# Triggerboard.net
KiCad netlist of a schematic drawn in EAGLE
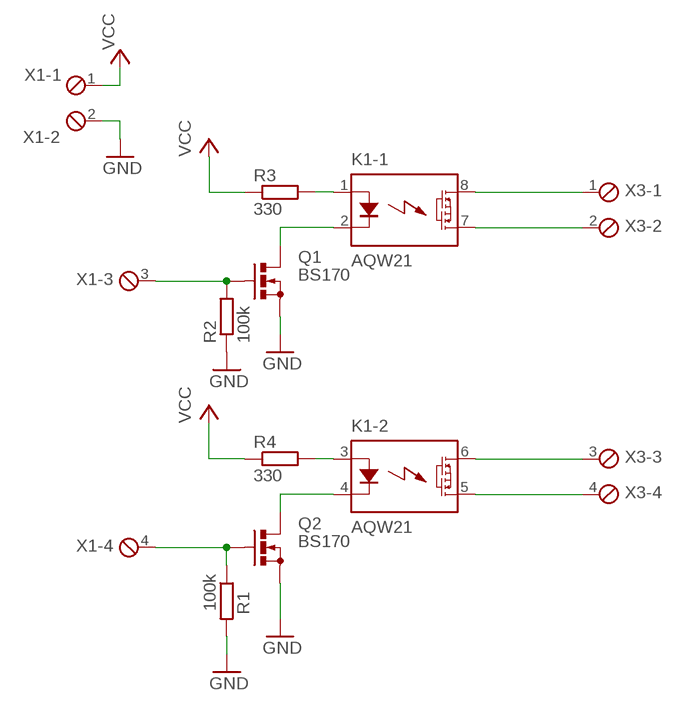
[diagram p0: schematic, sheet 1]

(export (version "E")
  (design (tool "Eeschema 10.0.6"))
  (components
    (comp (ref "K1")
      (value "AQW21")
      (footprint "eagle-import:DIL08")
      (fields
        (field (name "MF") "PANASONIC")
        (field (name "MPN") "AQW210EH")
        (field (name "OC_NEWARK") "10C3902")
      )
      (libsource (lib "eagle-import") (part "AQW21"))
    )
    (comp (ref "Q1")
      (value "BS170")
      (footprint "eagle-import:SOT54E")
      (fields (field (name "MF") "ON SEMICONDUCTOR"))
      (libsource (lib "eagle-import") (part "BS170"))
    )
    (comp (ref "Q2")
      (value "BS170")
      (footprint "eagle-import:SOT54E")
      (fields (field (name "MF") "ON SEMICONDUCTOR"))
      (libsource (lib "eagle-import") (part "BS170"))
    )
    (comp (ref "R1")
      (value "100k")
      (footprint "eagle-import:0207_12")
      (libsource (lib "eagle-import") (part "R-EU_0207/12"))
    )
    (comp (ref "R2")
      (value "100k")
      (footprint "eagle-import:0207_12")
      (libsource (lib "eagle-import") (part "R-EU_0207/12"))
    )
    (comp (ref "R3")
      (value "330")
      (footprint "eagle-import:0207_12")
      (fields (field (name "MF") "MULTICOMP PRO") (field (name "MPN") "MCF 1W 330R"))
      (libsource (lib "eagle-import") (part "R-EU_0207/12"))
    )
    (comp (ref "R4")
      (value "330")
      (footprint "eagle-import:0207_12")
      (fields (field (name "MF") "MULTICOMP PRO") (field (name "MPN") "MCF 1W 330R"))
      (libsource (lib "eagle-import") (part "R-EU_0207/12"))
    )
    (comp (ref "X1")
      (value "MPT4")
      (footprint "eagle-import:4POL254")
      (libsource (lib "eagle-import") (part "MPT4"))
    )
    (comp (ref "X3")
      (value "MPT4")
      (footprint "eagle-import:4POL254")
      (libsource (lib "eagle-import") (part "MPT4"))
    )
  )
  (nets
    (net (code "1") (name "GND") (class "Default")
      (node (ref "Q1") (pin "S") (pinfunction "S_S") (pintype "passive"))
      (node (ref "Q2") (pin "S") (pinfunction "S_S") (pintype "passive"))
      (node (ref "R1") (pin "2") (pinfunction "2_2") (pintype "passive"))
      (node (ref "R2") (pin "1") (pinfunction "1_1") (pintype "passive"))
      (node (ref "X1") (pin "2") (pinfunction "1_2") (pintype "passive"))
    )
    (net (code "2") (name "Net-(K1A-A)") (class "Default")
      (node (ref "K1") (pin "1") (pinfunction "A_1") (pintype "passive"))
      (node (ref "R3") (pin "2") (pinfunction "2_2") (pintype "passive"))
    )
    (net (code "3") (name "Net-(K1A-D1)") (class "Default")
      (node (ref "K1") (pin "8") (pinfunction "D1_8") (pintype "passive"))
      (node (ref "X3") (pin "1") (pinfunction "1_1") (pintype "passive"))
    )
    (net (code "4") (name "Net-(K1A-D2)") (class "Default")
      (node (ref "K1") (pin "7") (pinfunction "D2_7") (pintype "passive"))
      (node (ref "X3") (pin "2") (pinfunction "1_2") (pintype "passive"))
    )
    (net (code "5") (name "Net-(K1A-K)") (class "Default")
      (node (ref "K1") (pin "2") (pinfunction "K_2") (pintype "passive"))
      (node (ref "Q1") (pin "D") (pinfunction "D_D") (pintype "passive"))
    )
    (net (code "6") (name "Net-(K1B-A)") (class "Default")
      (node (ref "K1") (pin "3") (pinfunction "A_3") (pintype "passive"))
      (node (ref "R4") (pin "2") (pinfunction "2_2") (pintype "passive"))
    )
    (net (code "7") (name "Net-(K1B-D1)") (class "Default")
      (node (ref "K1") (pin "6") (pinfunction "D1_6") (pintype "passive"))
      (node (ref "X3") (pin "3") (pinfunction "1_3") (pintype "passive"))
    )
    (net (code "8") (name "Net-(K1B-D2)") (class "Default")
      (node (ref "K1") (pin "5") (pinfunction "D2_5") (pintype "passive"))
      (node (ref "X3") (pin "4") (pinfunction "1_4") (pintype "passive"))
    )
    (net (code "9") (name "Net-(K1B-K)") (class "Default")
      (node (ref "K1") (pin "4") (pinfunction "K_4") (pintype "passive"))
      (node (ref "Q2") (pin "D") (pinfunction "D_D") (pintype "passive"))
    )
    (net (code "10") (name "Net-(X1C-1)") (class "Default")
      (node (ref "Q1") (pin "G") (pinfunction "G_G") (pintype "passive"))
      (node (ref "R2") (pin "2") (pinfunction "2_2") (pintype "passive"))
      (node (ref "X1") (pin "3") (pinfunction "1_3") (pintype "passive"))
    )
    (net (code "11") (name "Net-(X1D-1)") (class "Default")
      (node (ref "Q2") (pin "G") (pinfunction "G_G") (pintype "passive"))
      (node (ref "R1") (pin "1") (pinfunction "1_1") (pintype "passive"))
      (node (ref "X1") (pin "4") (pinfunction "1_4") (pintype "passive"))
    )
    (net (code "12") (name "VCC") (class "Default")
      (node (ref "R3") (pin "1") (pinfunction "1_1") (pintype "passive"))
      (node (ref "R4") (pin "1") (pinfunction "1_1") (pintype "passive"))
      (node (ref "X1") (pin "1") (pinfunction "1_1") (pintype "passive"))
    )
  )
)
